# IDC_distributor.net
KiCad netlist of a schematic drawn in EAGLE
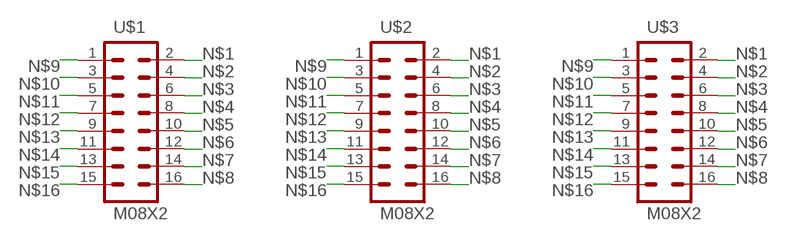
[diagram p0: schematic, sheet 1]

(export (version "E")
  (design (tool "Eeschema 10.0.6"))
  (components
    (comp (ref "U$1")
      (value "M08X2")
      (footprint "eagle-import:2X8")
      (libsource (lib "eagle-import") (part "M08X2"))
    )
    (comp (ref "U$2")
      (value "M08X2")
      (footprint "eagle-import:2X8")
      (libsource (lib "eagle-import") (part "M08X2"))
    )
    (comp (ref "U$3")
      (value "M08X2")
      (footprint "eagle-import:2X8")
      (libsource (lib "eagle-import") (part "M08X2"))
    )
  )
  (nets
    (net (code "1") (name "/N$1") (class "Default")
      (node (ref "U$1") (pin "2") (pinfunction "2_2") (pintype "passive"))
      (node (ref "U$2") (pin "2") (pinfunction "2_2") (pintype "passive"))
      (node (ref "U$3") (pin "2") (pinfunction "2_2") (pintype "passive"))
    )
    (net (code "2") (name "/N$2") (class "Default")
      (node (ref "U$1") (pin "4") (pinfunction "4_4") (pintype "passive"))
      (node (ref "U$2") (pin "4") (pinfunction "4_4") (pintype "passive"))
      (node (ref "U$3") (pin "4") (pinfunction "4_4") (pintype "passive"))
    )
    (net (code "3") (name "/N$3") (class "Default")
      (node (ref "U$1") (pin "6") (pinfunction "6_6") (pintype "passive"))
      (node (ref "U$2") (pin "6") (pinfunction "6_6") (pintype "passive"))
      (node (ref "U$3") (pin "6") (pinfunction "6_6") (pintype "passive"))
    )
    (net (code "4") (name "/N$4") (class "Default")
      (node (ref "U$1") (pin "8") (pinfunction "8_8") (pintype "passive"))
      (node (ref "U$2") (pin "8") (pinfunction "8_8") (pintype "passive"))
      (node (ref "U$3") (pin "8") (pinfunction "8_8") (pintype "passive"))
    )
    (net (code "5") (name "/N$5") (class "Default")
      (node (ref "U$1") (pin "10") (pinfunction "10_10") (pintype "passive"))
      (node (ref "U$2") (pin "10") (pinfunction "10_10") (pintype "passive"))
      (node (ref "U$3") (pin "10") (pinfunction "10_10") (pintype "passive"))
    )
    (net (code "6") (name "/N$6") (class "Default")
      (node (ref "U$1") (pin "12") (pinfunction "12_12") (pintype "passive"))
      (node (ref "U$2") (pin "12") (pinfunction "12_12") (pintype "passive"))
      (node (ref "U$3") (pin "12") (pinfunction "12_12") (pintype "passive"))
    )
    (net (code "7") (name "/N$7") (class "Default")
      (node (ref "U$1") (pin "14") (pinfunction "14_14") (pintype "passive"))
      (node (ref "U$2") (pin "14") (pinfunction "14_14") (pintype "passive"))
      (node (ref "U$3") (pin "14") (pinfunction "14_14") (pintype "passive"))
    )
    (net (code "8") (name "/N$8") (class "Default")
      (node (ref "U$1") (pin "16") (pinfunction "16_16") (pintype "passive"))
      (node (ref "U$2") (pin "16") (pinfunction "16_16") (pintype "passive"))
      (node (ref "U$3") (pin "16") (pinfunction "16_16") (pintype "passive"))
    )
    (net (code "9") (name "/N$9") (class "Default")
      (node (ref "U$1") (pin "1") (pinfunction "1_1") (pintype "passive"))
      (node (ref "U$2") (pin "1") (pinfunction "1_1") (pintype "passive"))
      (node (ref "U$3") (pin "1") (pinfunction "1_1") (pintype "passive"))
    )
    (net (code "10") (name "/N$10") (class "Default")
      (node (ref "U$1") (pin "3") (pinfunction "3_3") (pintype "passive"))
      (node (ref "U$2") (pin "3") (pinfunction "3_3") (pintype "passive"))
      (node (ref "U$3") (pin "3") (pinfunction "3_3") (pintype "passive"))
    )
    (net (code "11") (name "/N$11") (class "Default")
      (node (ref "U$1") (pin "5") (pinfunction "5_5") (pintype "passive"))
      (node (ref "U$2") (pin "5") (pinfunction "5_5") (pintype "passive"))
      (node (ref "U$3") (pin "5") (pinfunction "5_5") (pintype "passive"))
    )
    (net (code "12") (name "/N$12") (class "Default")
      (node (ref "U$1") (pin "7") (pinfunction "7_7") (pintype "passive"))
      (node (ref "U$2") (pin "7") (pinfunction "7_7") (pintype "passive"))
      (node (ref "U$3") (pin "7") (pinfunction "7_7") (pintype "passive"))
    )
    (net (code "13") (name "/N$13") (class "Default")
      (node (ref "U$1") (pin "9") (pinfunction "9_9") (pintype "passive"))
      (node (ref "U$2") (pin "9") (pinfunction "9_9") (pintype "passive"))
      (node (ref "U$3") (pin "9") (pinfunction "9_9") (pintype "passive"))
    )
    (net (code "14") (name "/N$14") (class "Default")
      (node (ref "U$1") (pin "11") (pinfunction "11_11") (pintype "passive"))
      (node (ref "U$2") (pin "11") (pinfunction "11_11") (pintype "passive"))
      (node (ref "U$3") (pin "11") (pinfunction "11_11") (pintype "passive"))
    )
    (net (code "15") (name "/N$15") (class "Default")
      (node (ref "U$1") (pin "13") (pinfunction "13_13") (pintype "passive"))
      (node (ref "U$2") (pin "13") (pinfunction "13_13") (pintype "passive"))
      (node (ref "U$3") (pin "13") (pinfunction "13_13") (pintype "passive"))
    )
    (net (code "16") (name "/N$16") (class "Default")
      (node (ref "U$1") (pin "15") (pinfunction "15_15") (pintype "passive"))
      (node (ref "U$2") (pin "15") (pinfunction "15_15") (pintype "passive"))
      (node (ref "U$3") (pin "15") (pinfunction "15_15") (pintype "passive"))
    )
  )
)
